# FieldsCore.net
KiCad netlist of a schematic drawn in EAGLE
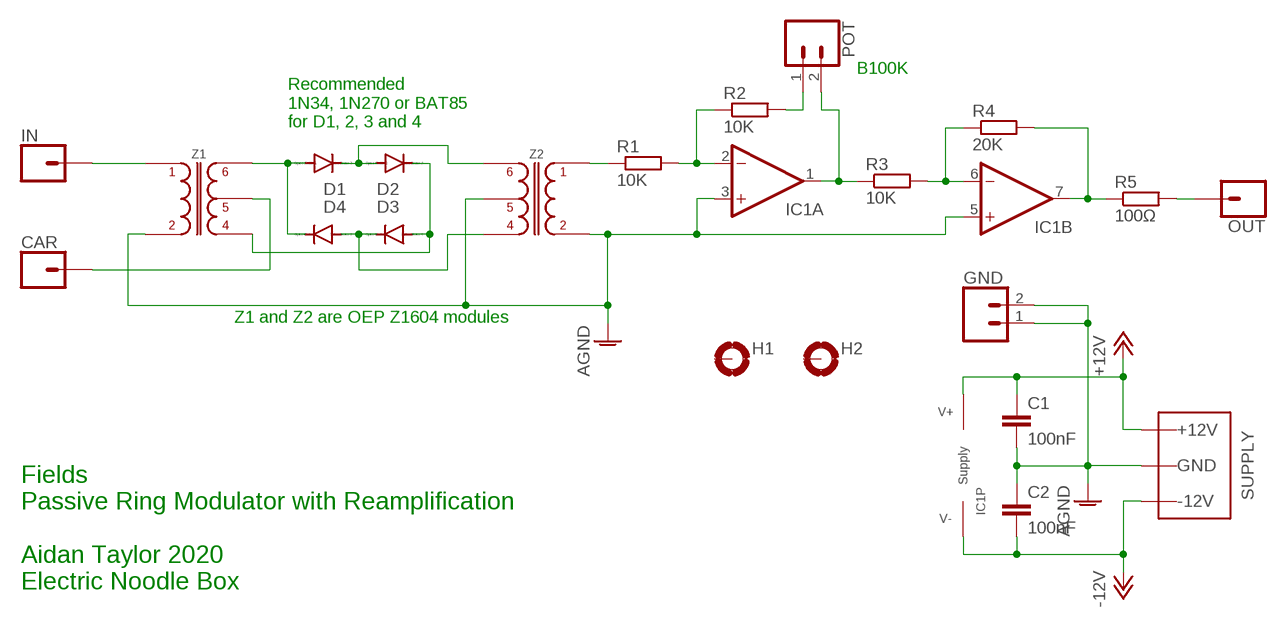
[diagram p0: schematic, sheet 1]

(export (version "E")
  (design (tool "Eeschema 10.0.6"))
  (components
    (comp (ref "C1")
      (value "100nF")
      (footprint "eagle-import:C050-025X075")
      (libsource (lib "eagle-import") (part "C-EU050-025X075"))
    )
    (comp (ref "C2")
      (value "100nF")
      (footprint "eagle-import:C050-025X075")
      (libsource (lib "eagle-import") (part "C-EU050-025X075"))
    )
    (comp (ref "CAR")
      (value "1XWIREPAD")
      (footprint "eagle-import:1X01")
      (libsource (lib "eagle-import") (part "1XWIREPAD"))
    )
    (comp (ref "D1")
      (value "DIODE-DO35-10")
      (footprint "eagle-import:DO35-10")
      (libsource (lib "eagle-import") (part "DIODE-DO35-10"))
    )
    (comp (ref "D2")
      (value "DIODE-DO35-10")
      (footprint "eagle-import:DO35-10")
      (libsource (lib "eagle-import") (part "DIODE-DO35-10"))
    )
    (comp (ref "D3")
      (value "DIODE-DO35-10")
      (footprint "eagle-import:DO35-10")
      (libsource (lib "eagle-import") (part "DIODE-DO35-10"))
    )
    (comp (ref "D4")
      (value "DIODE-DO35-10")
      (footprint "eagle-import:DO35-10")
      (libsource (lib "eagle-import") (part "DIODE-DO35-10"))
    )
    (comp (ref "GND")
      (value "2XWIREPAD")
      (footprint "eagle-import:1X02")
      (libsource (lib "eagle-import") (part "2XWIREPAD"))
    )
    (comp (ref "H1")
      (value "MOUNT-PAD-ROUND3.2")
      (footprint "eagle-import:3,2-PAD")
      (libsource (lib "eagle-import") (part "MOUNT-PAD-ROUND3.2"))
    )
    (comp (ref "H2")
      (value "MOUNT-PAD-ROUND3.2")
      (footprint "eagle-import:3,2-PAD")
      (libsource (lib "eagle-import") (part "MOUNT-PAD-ROUND3.2"))
    )
    (comp (ref "IC1")
      (value "TL0X2DIL")
      (footprint "eagle-import:DIL08")
      (libsource (lib "eagle-import") (part "TL0X2DIL"))
    )
    (comp (ref "IN")
      (value "1XWIREPAD")
      (footprint "eagle-import:1X01")
      (libsource (lib "eagle-import") (part "1XWIREPAD"))
    )
    (comp (ref "OUT")
      (value "1XWIREPAD")
      (footprint "eagle-import:1X01")
      (libsource (lib "eagle-import") (part "1XWIREPAD"))
    )
    (comp (ref "POT")
      (value "2XWIREPAD")
      (footprint "eagle-import:1X02")
      (libsource (lib "eagle-import") (part "2XWIREPAD"))
    )
    (comp (ref "R1")
      (value "10K")
      (footprint "eagle-import:0207_10")
      (libsource (lib "eagle-import") (part "R-EU_0207/10"))
    )
    (comp (ref "R2")
      (value "10K")
      (footprint "eagle-import:0207_10")
      (libsource (lib "eagle-import") (part "R-EU_0207/10"))
    )
    (comp (ref "R3")
      (value "10K")
      (footprint "eagle-import:0207_10")
      (libsource (lib "eagle-import") (part "R-EU_0207/10"))
    )
    (comp (ref "R4")
      (value "20K")
      (footprint "eagle-import:0207_10")
      (libsource (lib "eagle-import") (part "R-EU_0207/10"))
    )
    (comp (ref "R5")
      (value "100Ω")
      (footprint "eagle-import:0207_10")
      (libsource (lib "eagle-import") (part "R-EU_0207/10"))
    )
    (comp (ref "WP1")
      (value "COMBO_SUPPLY_HEADER")
      (footprint "eagle-import:COMBINED_POWER")
      (libsource (lib "eagle-import") (part "COMBO_SUPPLY_HEADER"))
    )
    (comp (ref "Z1")
      (value "Z1604_AUDIO_TRANSFORMER")
      (footprint "eagle-import:Z1604_TRANSFORMER")
      (libsource (lib "eagle-import") (part "Z1604_AUDIO_TRANSFORMER"))
    )
    (comp (ref "Z2")
      (value "Z1604_AUDIO_TRANSFORMER")
      (footprint "eagle-import:Z1604_TRANSFORMER")
      (libsource (lib "eagle-import") (part "Z1604_AUDIO_TRANSFORMER"))
    )
  )
  (nets
    (net (code "1") (name "+12V") (class "Default")
      (node (ref "C1") (pin "1") (pinfunction "1_1") (pintype "passive"))
      (node (ref "IC1") (pin "8") (pinfunction "V+_8") (pintype "bidirectional"))
      (node (ref "WP1") (pin "V+1") (pinfunction "V++_V+1") (pintype "power_in"))
      (node (ref "WP1") (pin "V+2") (pinfunction "V++_V+2") (pintype "power_in"))
      (node (ref "WP1") (pin "V+3") (pinfunction "V++_V+3") (pintype "power_in"))
    )
    (net (code "2") (name "-12V") (class "Default")
      (node (ref "C2") (pin "2") (pinfunction "2_2") (pintype "passive"))
      (node (ref "IC1") (pin "4") (pinfunction "V-_4") (pintype "bidirectional"))
      (node (ref "WP1") (pin "V-1") (pinfunction "V--_V-1") (pintype "power_in"))
      (node (ref "WP1") (pin "V-2") (pinfunction "V--_V-2") (pintype "power_in"))
      (node (ref "WP1") (pin "V-3") (pinfunction "V--_V-3") (pintype "power_in"))
    )
    (net (code "3") (name "AGND") (class "Default")
      (node (ref "C1") (pin "2") (pinfunction "2_2") (pintype "passive"))
      (node (ref "C2") (pin "1") (pinfunction "1_1") (pintype "passive"))
      (node (ref "GND") (pin "1") (pinfunction "1_1") (pintype "passive"))
      (node (ref "GND") (pin "2") (pinfunction "2_2") (pintype "passive"))
      (node (ref "IC1") (pin "3") (pinfunction "+IN_3") (pintype "input"))
      (node (ref "IC1") (pin "5") (pinfunction "+IN_5") (pintype "input"))
      (node (ref "WP1") (pin "GND1") (pinfunction "AGND_GND1") (pintype "power_in"))
      (node (ref "WP1") (pin "GND2") (pinfunction "AGND_GND2") (pintype "power_in"))
      (node (ref "WP1") (pin "GND3") (pinfunction "AGND_GND3") (pintype "power_in"))
      (node (ref "WP1") (pin "GND4") (pinfunction "AGND_GND4") (pintype "power_in"))
      (node (ref "WP1") (pin "GND5") (pinfunction "AGND_GND5") (pintype "power_in"))
      (node (ref "WP1") (pin "GND6") (pinfunction "AGND_GND6") (pintype "power_in"))
      (node (ref "WP1") (pin "GND7") (pinfunction "AGND_GND7") (pintype "power_in"))
      (node (ref "WP1") (pin "GND8") (pinfunction "AGND_GND8") (pintype "power_in"))
      (node (ref "Z1") (pin "T3") (pinfunction "3_T3") (pintype "bidirectional"))
      (node (ref "Z2") (pin "T3") (pinfunction "3_T3") (pintype "bidirectional"))
      (node (ref "Z2") (pin "T5") (pinfunction "5_T5") (pintype "bidirectional"))
    )
    (net (code "4") (name "Net-(IC1A--IN)") (class "Default")
      (node (ref "IC1") (pin "2") (pinfunction "-IN_2") (pintype "input"))
      (node (ref "R1") (pin "2") (pinfunction "2_2") (pintype "passive"))
      (node (ref "R2") (pin "1") (pinfunction "1_1") (pintype "passive"))
    )
    (net (code "5") (name "Net-(IC1A-OUT)") (class "Default")
      (node (ref "IC1") (pin "1") (pinfunction "OUT_1") (pintype "output"))
      (node (ref "POT") (pin "2") (pinfunction "2_2") (pintype "passive"))
      (node (ref "R3") (pin "1") (pinfunction "1_1") (pintype "passive"))
    )
    (net (code "6") (name "Net-(IC1B--IN)") (class "Default")
      (node (ref "IC1") (pin "6") (pinfunction "-IN_6") (pintype "input"))
      (node (ref "R3") (pin "2") (pinfunction "2_2") (pintype "passive"))
      (node (ref "R4") (pin "1") (pinfunction "1_1") (pintype "passive"))
    )
    (net (code "7") (name "Net-(IC1B-OUT)") (class "Default")
      (node (ref "IC1") (pin "7") (pinfunction "OUT_7") (pintype "output"))
      (node (ref "R4") (pin "2") (pinfunction "2_2") (pintype "passive"))
      (node (ref "R5") (pin "1") (pinfunction "1_1") (pintype "passive"))
    )
    (net (code "8") (name "Net-(OUT-Pad1)") (class "Default")
      (node (ref "OUT") (pin "1") (pinfunction "1_1") (pintype "passive"))
      (node (ref "R5") (pin "2") (pinfunction "2_2") (pintype "passive"))
    )
    (net (code "9") (name "Net-(POT-Pad1)") (class "Default")
      (node (ref "POT") (pin "1") (pinfunction "1_1") (pintype "passive"))
      (node (ref "R2") (pin "2") (pinfunction "2_2") (pintype "passive"))
    )
    (net (code "10") (name "Net-(Z1-1)") (class "Default")
      (node (ref "IN") (pin "1") (pinfunction "1_1") (pintype "passive"))
      (node (ref "Z1") (pin "T1") (pinfunction "1_T1") (pintype "bidirectional"))
    )
    (net (code "11") (name "Net-(Z1-4)") (class "Default")
      (node (ref "D2") (pin "C") (pinfunction "C_C") (pintype "passive"))
      (node (ref "D3") (pin "A") (pinfunction "A_A") (pintype "passive"))
      (node (ref "Z1") (pin "T4") (pinfunction "4_T4") (pintype "bidirectional"))
    )
    (net (code "12") (name "Net-(Z1-5)") (class "Default")
      (node (ref "CAR") (pin "1") (pinfunction "1_1") (pintype "passive"))
      (node (ref "Z1") (pin "T5") (pinfunction "5_T5") (pintype "bidirectional"))
    )
    (net (code "13") (name "Net-(Z1-6)") (class "Default")
      (node (ref "D1") (pin "A") (pinfunction "A_A") (pintype "passive"))
      (node (ref "D4") (pin "C") (pinfunction "C_C") (pintype "passive"))
      (node (ref "Z1") (pin "T6") (pinfunction "6_T6") (pintype "bidirectional"))
    )
    (net (code "14") (name "Net-(Z2-1)") (class "Default")
      (node (ref "R1") (pin "1") (pinfunction "1_1") (pintype "passive"))
      (node (ref "Z2") (pin "T1") (pinfunction "1_T1") (pintype "bidirectional"))
    )
    (net (code "15") (name "Net-(Z2-4)") (class "Default")
      (node (ref "D3") (pin "C") (pinfunction "C_C") (pintype "passive"))
      (node (ref "D4") (pin "A") (pinfunction "A_A") (pintype "passive"))
      (node (ref "Z2") (pin "T4") (pinfunction "4_T4") (pintype "bidirectional"))
    )
    (net (code "16") (name "Net-(Z2-6)") (class "Default")
      (node (ref "D1") (pin "C") (pinfunction "C_C") (pintype "passive"))
      (node (ref "D2") (pin "A") (pinfunction "A_A") (pintype "passive"))
      (node (ref "Z2") (pin "T6") (pinfunction "6_T6") (pintype "bidirectional"))
    )
    (net (code "17") (name "unconnected-(H1-MOUNT-PadB3,2)") (class "Default")
      (node (ref "H1") (pin "B3,2") (pinfunction "MOUNT_B3,2") (pintype "passive"))
    )
    (net (code "18") (name "unconnected-(H2-MOUNT-PadB3,2)") (class "Default")
      (node (ref "H2") (pin "B3,2") (pinfunction "MOUNT_B3,2") (pintype "passive"))
    )
  )
)
